# OMSI_TABLE_R12_v2.net
KiCad netlist of a schematic drawn in EAGLE
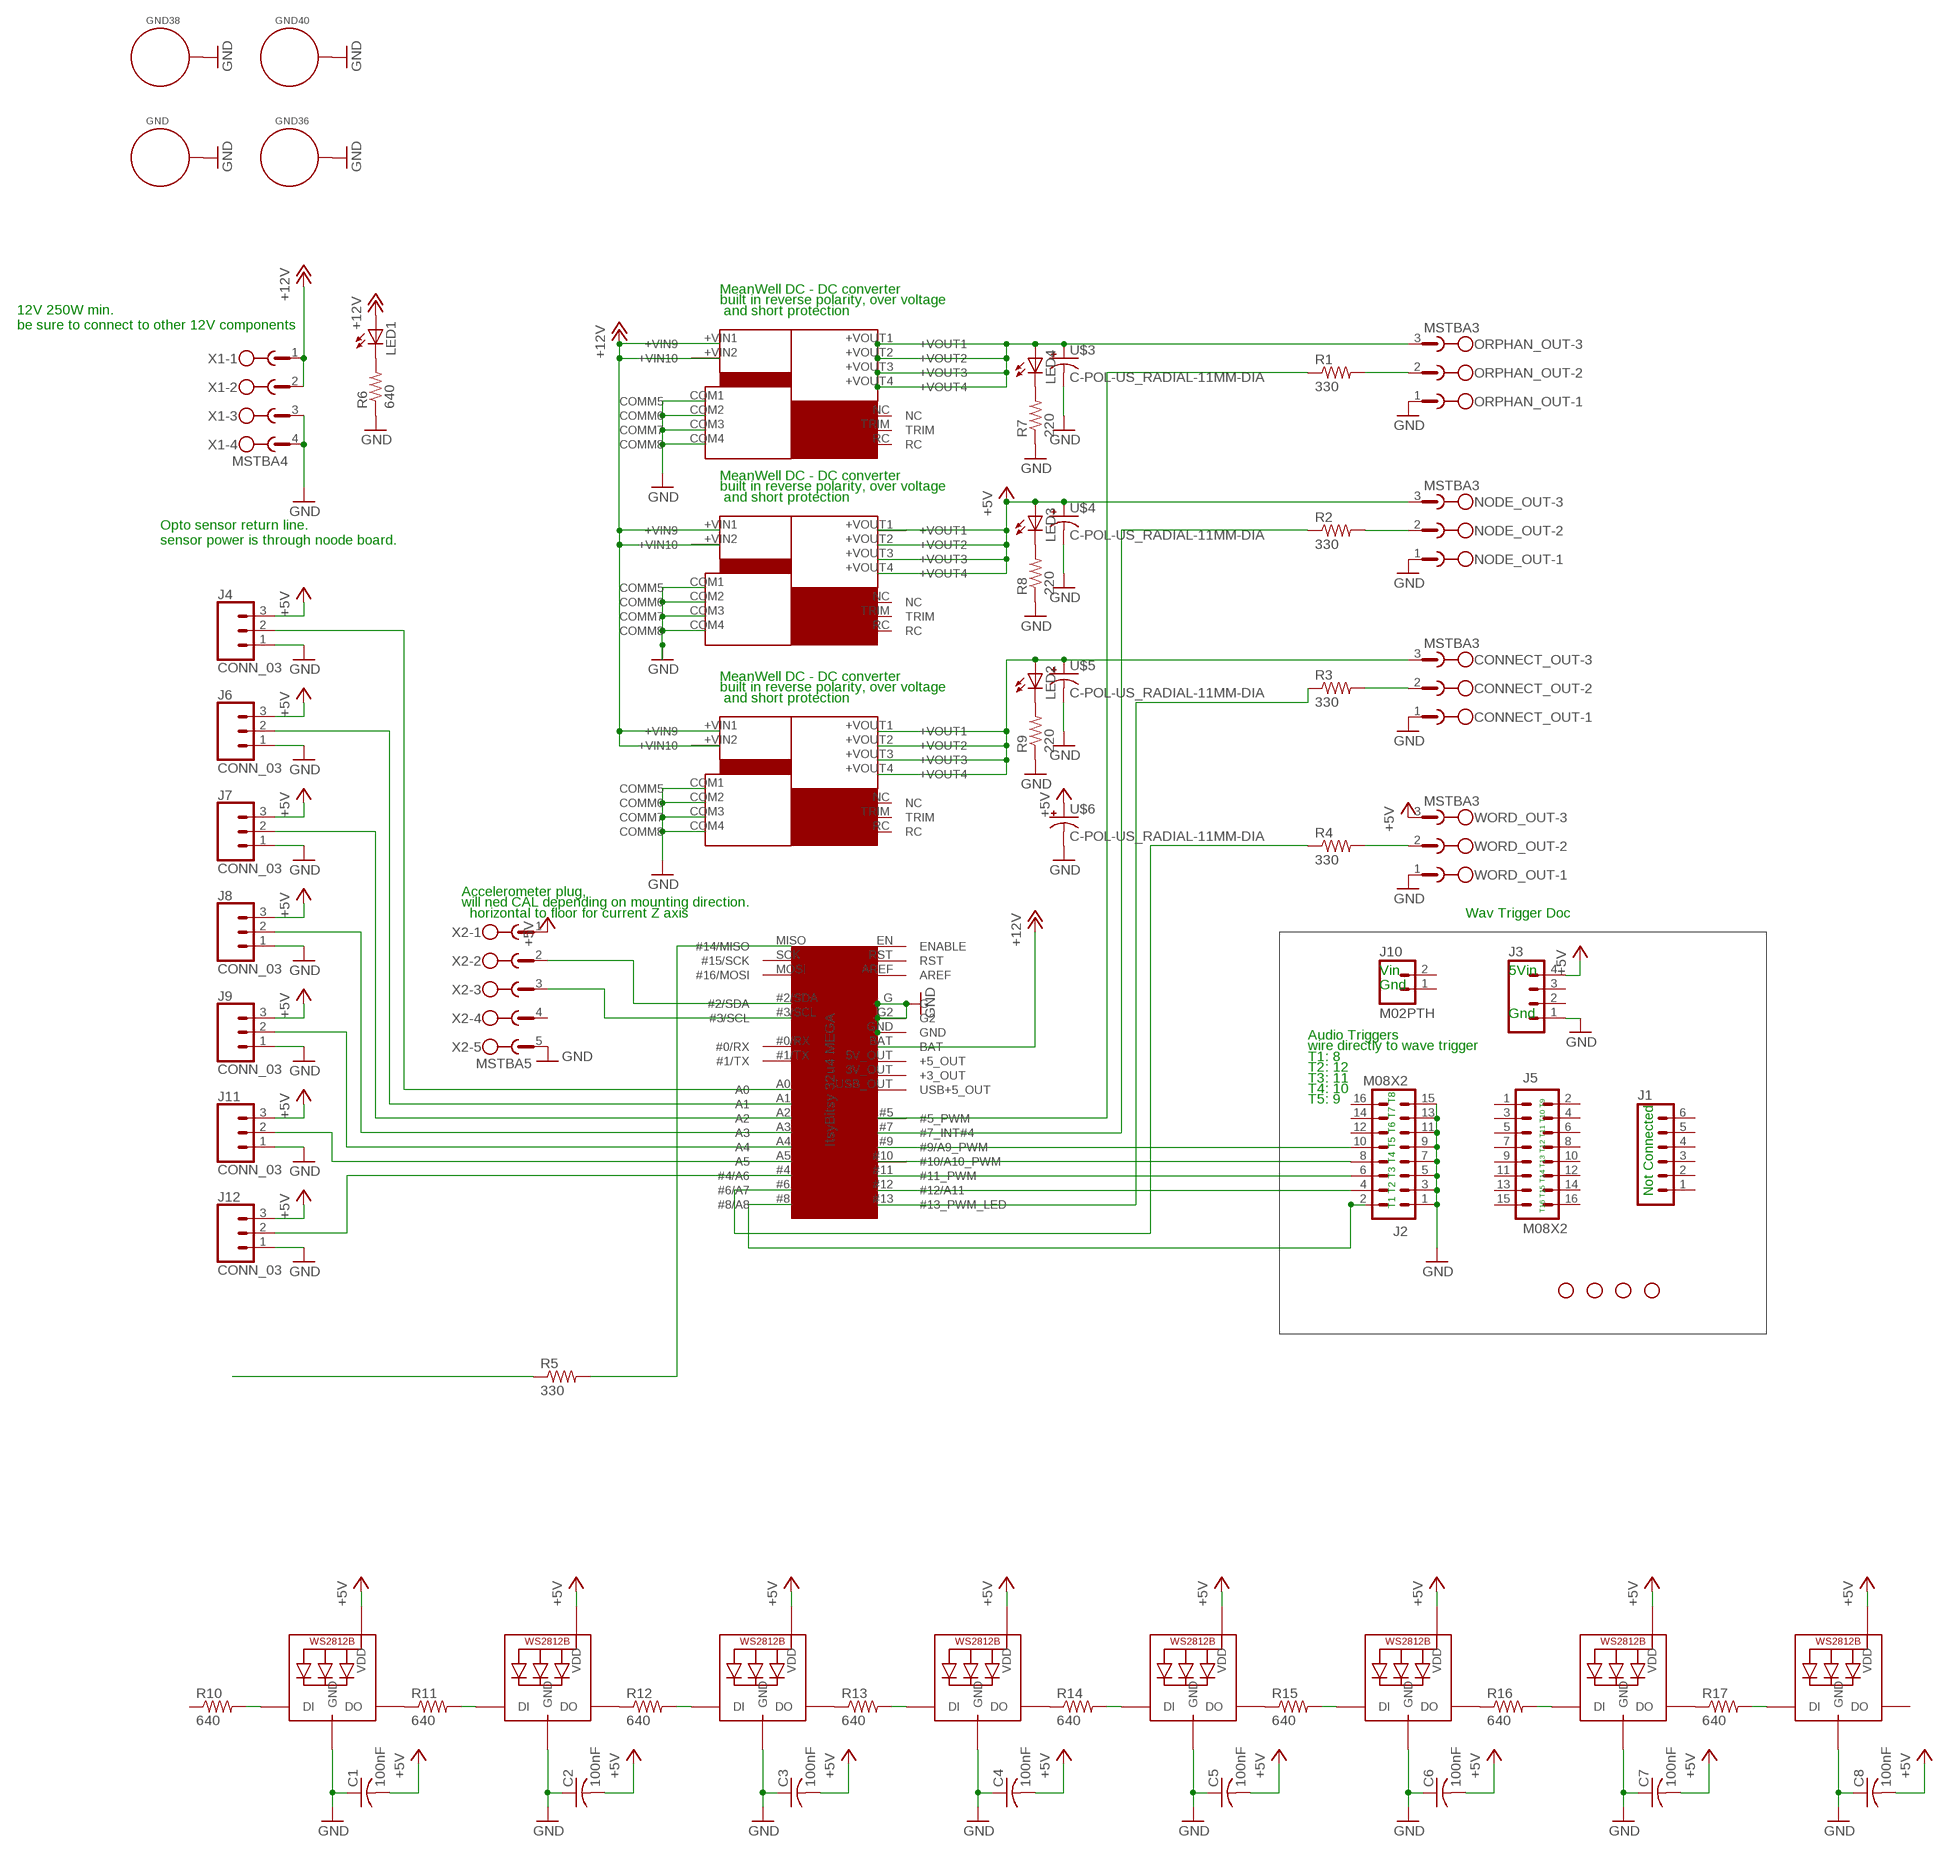
[diagram p0: schematic, sheet 1]

(export (version "E")
  (design (tool "Eeschema 10.0.6"))
  (components
    (comp (ref "C1")
      (value "100nF")
      (footprint "eagle-import:C0805")
      (libsource (lib "eagle-import") (part "C-USC0805"))
    )
    (comp (ref "C2")
      (value "100nF")
      (footprint "eagle-import:C0805")
      (libsource (lib "eagle-import") (part "C-USC0805"))
    )
    (comp (ref "C3")
      (value "100nF")
      (footprint "eagle-import:C0805")
      (libsource (lib "eagle-import") (part "C-USC0805"))
    )
    (comp (ref "C4")
      (value "100nF")
      (footprint "eagle-import:C0805")
      (libsource (lib "eagle-import") (part "C-USC0805"))
    )
    (comp (ref "C5")
      (value "100nF")
      (footprint "eagle-import:C0805")
      (libsource (lib "eagle-import") (part "C-USC0805"))
    )
    (comp (ref "C6")
      (value "100nF")
      (footprint "eagle-import:C0805")
      (libsource (lib "eagle-import") (part "C-USC0805"))
    )
    (comp (ref "C7")
      (value "100nF")
      (footprint "eagle-import:C0805")
      (libsource (lib "eagle-import") (part "C-USC0805"))
    )
    (comp (ref "C8")
      (value "100nF")
      (footprint "eagle-import:C0805")
      (libsource (lib "eagle-import") (part "C-USC0805"))
    )
    (comp (ref "CONNECT_OUT")
      (value "MSTBA3")
      (footprint "eagle-import:MSTBA3")
      (fields (field (name "MF") "FARNELL") (field (name "MPN") "1757255"))
      (libsource (lib "eagle-import") (part "MSTBA3"))
    )
    (comp (ref "GND")
      (value "STANDOFF_ELECTRICAL5-32")
      (footprint "eagle-import:STANDOFF_ELECTRICAL_5_32")
      (libsource (lib "eagle-import") (part "STANDOFF_ELECTRICAL5-32"))
    )
    (comp (ref "GND36")
      (value "STANDOFF_ELECTRICAL5-32")
      (footprint "eagle-import:STANDOFF_ELECTRICAL_5_32")
      (libsource (lib "eagle-import") (part "STANDOFF_ELECTRICAL5-32"))
    )
    (comp (ref "GND38")
      (value "STANDOFF_ELECTRICAL5-32")
      (footprint "eagle-import:STANDOFF_ELECTRICAL_5_32")
      (libsource (lib "eagle-import") (part "STANDOFF_ELECTRICAL5-32"))
    )
    (comp (ref "GND40")
      (value "STANDOFF_ELECTRICAL5-32")
      (footprint "eagle-import:STANDOFF_ELECTRICAL_5_32")
      (libsource (lib "eagle-import") (part "STANDOFF_ELECTRICAL5-32"))
    )
    (comp (ref "J1")
      (value "M06SIP")
      (footprint "eagle-import:1X06")
      (libsource (lib "eagle-import") (part "M06SIP"))
    )
    (comp (ref "J2")
      (value "M08X2")
      (footprint "eagle-import:2X8")
      (libsource (lib "eagle-import") (part "M08X2"))
    )
    (comp (ref "J3")
      (value "M04PTH")
      (footprint "eagle-import:1X04")
      (libsource (lib "eagle-import") (part "M04PTH"))
    )
    (comp (ref "J4")
      (value "CONN_03")
      (footprint "eagle-import:1X03_3.5MM_RA")
      (libsource (lib "eagle-import") (part "CONN_03"))
    )
    (comp (ref "J5")
      (value "M08X2")
      (footprint "eagle-import:2X8")
      (libsource (lib "eagle-import") (part "M08X2"))
    )
    (comp (ref "J6")
      (value "CONN_03")
      (footprint "eagle-import:1X03_3.5MM_RA")
      (libsource (lib "eagle-import") (part "CONN_03"))
    )
    (comp (ref "J7")
      (value "CONN_03")
      (footprint "eagle-import:1X03_3.5MM_RA")
      (libsource (lib "eagle-import") (part "CONN_03"))
    )
    (comp (ref "J8")
      (value "CONN_03")
      (footprint "eagle-import:1X03_3.5MM_RA")
      (libsource (lib "eagle-import") (part "CONN_03"))
    )
    (comp (ref "J9")
      (value "CONN_03")
      (footprint "eagle-import:1X03_3.5MM_RA")
      (libsource (lib "eagle-import") (part "CONN_03"))
    )
    (comp (ref "J10")
      (value "M02PTH")
      (footprint "eagle-import:1X02")
      (libsource (lib "eagle-import") (part "M02PTH"))
    )
    (comp (ref "J11")
      (value "CONN_03")
      (footprint "eagle-import:1X03_3.5MM_RA")
      (libsource (lib "eagle-import") (part "CONN_03"))
    )
    (comp (ref "J12")
      (value "CONN_03")
      (footprint "eagle-import:1X03_3.5MM_RA")
      (libsource (lib "eagle-import") (part "CONN_03"))
    )
    (comp (ref "LED1")
      (value "LEDCHIPLED_1206")
      (footprint "eagle-import:CHIPLED_1206")
      (libsource (lib "eagle-import") (part "LEDCHIPLED_1206"))
    )
    (comp (ref "LED2")
      (value "LEDCHIPLED_1206")
      (footprint "eagle-import:CHIPLED_1206")
      (libsource (lib "eagle-import") (part "LEDCHIPLED_1206"))
    )
    (comp (ref "LED3")
      (value "LEDCHIPLED_1206")
      (footprint "eagle-import:CHIPLED_1206")
      (libsource (lib "eagle-import") (part "LEDCHIPLED_1206"))
    )
    (comp (ref "LED4")
      (value "LEDCHIPLED_1206")
      (footprint "eagle-import:CHIPLED_1206")
      (libsource (lib "eagle-import") (part "LEDCHIPLED_1206"))
    )
    (comp (ref "LED5")
      (value "WS2812B")
      (footprint "eagle-import:WS2812D-F5")
      (libsource (lib "eagle-import") (part "WS2812B"))
    )
    (comp (ref "LED6")
      (value "WS2812B")
      (footprint "eagle-import:WS2812D-F5")
      (libsource (lib "eagle-import") (part "WS2812B"))
    )
    (comp (ref "LED7")
      (value "WS2812B")
      (footprint "eagle-import:WS2812D-F5")
      (libsource (lib "eagle-import") (part "WS2812B"))
    )
    (comp (ref "LED8")
      (value "WS2812B")
      (footprint "eagle-import:WS2812D-F5")
      (libsource (lib "eagle-import") (part "WS2812B"))
    )
    (comp (ref "LED9")
      (value "WS2812B")
      (footprint "eagle-import:WS2812D-F5")
      (libsource (lib "eagle-import") (part "WS2812B"))
    )
    (comp (ref "LED10")
      (value "WS2812B")
      (footprint "eagle-import:WS2812D-F5")
      (libsource (lib "eagle-import") (part "WS2812B"))
    )
    (comp (ref "LED11")
      (value "WS2812B")
      (footprint "eagle-import:WS2812D-F5")
      (libsource (lib "eagle-import") (part "WS2812B"))
    )
    (comp (ref "LED12")
      (value "WS2812B")
      (footprint "eagle-import:WS2812D-F5")
      (libsource (lib "eagle-import") (part "WS2812B"))
    )
    (comp (ref "MEANWELL_NID100_1")
      (value "MEANWELL_NID100")
      (footprint "eagle-import:MEANWELL_NID100")
      (libsource (lib "eagle-import") (part "MEANWELL_NID100"))
    )
    (comp (ref "MEANWELL_NID100_2")
      (value "MEANWELL_NID100")
      (footprint "eagle-import:MEANWELL_NID100")
      (libsource (lib "eagle-import") (part "MEANWELL_NID100"))
    )
    (comp (ref "MEANWELL_NID100_3")
      (value "MEANWELL_NID100")
      (footprint "eagle-import:MEANWELL_NID100")
      (libsource (lib "eagle-import") (part "MEANWELL_NID100"))
    )
    (comp (ref "NODE_OUT")
      (value "MSTBA3")
      (footprint "eagle-import:MSTBA3")
      (fields (field (name "MF") "FARNELL") (field (name "MPN") "1757255"))
      (libsource (lib "eagle-import") (part "MSTBA3"))
    )
    (comp (ref "ORPHAN_OUT")
      (value "MSTBA3")
      (footprint "eagle-import:MSTBA3")
      (fields (field (name "MF") "FARNELL") (field (name "MPN") "1757255"))
      (libsource (lib "eagle-import") (part "MSTBA3"))
    )
    (comp (ref "R1")
      (value "330")
      (footprint "eagle-import:RESAD1176W63L850D250B")
      (libsource (lib "eagle-import") (part "R-USAXIAL-11.7MM-PITCH_"))
    )
    (comp (ref "R2")
      (value "330")
      (footprint "eagle-import:RESAD1176W63L850D250B")
      (libsource (lib "eagle-import") (part "R-USAXIAL-11.7MM-PITCH_"))
    )
    (comp (ref "R3")
      (value "330")
      (footprint "eagle-import:RESAD1176W63L850D250B")
      (libsource (lib "eagle-import") (part "R-USAXIAL-11.7MM-PITCH_"))
    )
    (comp (ref "R4")
      (value "330")
      (footprint "eagle-import:RESAD1176W63L850D250B")
      (libsource (lib "eagle-import") (part "R-USAXIAL-11.7MM-PITCH_"))
    )
    (comp (ref "R5")
      (value "330")
      (footprint "eagle-import:RESAD1176W63L850D250B")
      (libsource (lib "eagle-import") (part "R-USAXIAL-11.7MM-PITCH_"))
    )
    (comp (ref "R6")
      (value "640")
      (footprint "eagle-import:R0805")
      (libsource (lib "eagle-import") (part "adafruit_420_R-US_R0805"))
    )
    (comp (ref "R7")
      (value "220")
      (footprint "eagle-import:R0805")
      (libsource (lib "eagle-import") (part "R-US_R0805"))
    )
    (comp (ref "R8")
      (value "220")
      (footprint "eagle-import:R0805")
      (libsource (lib "eagle-import") (part "R-US_R0805"))
    )
    (comp (ref "R9")
      (value "220")
      (footprint "eagle-import:R0805")
      (libsource (lib "eagle-import") (part "R-US_R0805"))
    )
    (comp (ref "R10")
      (value "640")
      (footprint "eagle-import:R0805")
      (libsource (lib "eagle-import") (part "adafruit_420_R-US_R0805"))
    )
    (comp (ref "R11")
      (value "640")
      (footprint "eagle-import:R0805")
      (libsource (lib "eagle-import") (part "adafruit_420_R-US_R0805"))
    )
    (comp (ref "R12")
      (value "640")
      (footprint "eagle-import:R0805")
      (libsource (lib "eagle-import") (part "adafruit_420_R-US_R0805"))
    )
    (comp (ref "R13")
      (value "640")
      (footprint "eagle-import:R0805")
      (libsource (lib "eagle-import") (part "adafruit_420_R-US_R0805"))
    )
    (comp (ref "R14")
      (value "640")
      (footprint "eagle-import:R0805")
      (libsource (lib "eagle-import") (part "adafruit_420_R-US_R0805"))
    )
    (comp (ref "R15")
      (value "640")
      (footprint "eagle-import:R0805")
      (libsource (lib "eagle-import") (part "adafruit_420_R-US_R0805"))
    )
    (comp (ref "R16")
      (value "640")
      (footprint "eagle-import:R0805")
      (libsource (lib "eagle-import") (part "adafruit_420_R-US_R0805"))
    )
    (comp (ref "R17")
      (value "640")
      (footprint "eagle-import:R0805")
      (libsource (lib "eagle-import") (part "adafruit_420_R-US_R0805"))
    )
    (comp (ref "STANDOFF5")
      (value "STAND-OFF")
      (footprint "eagle-import:STAND-OFF")
      (libsource (lib "eagle-import") (part "STAND-OFF"))
    )
    (comp (ref "STANDOFF6")
      (value "STAND-OFF")
      (footprint "eagle-import:STAND-OFF")
      (libsource (lib "eagle-import") (part "STAND-OFF"))
    )
    (comp (ref "STANDOFF7")
      (value "STAND-OFF")
      (footprint "eagle-import:STAND-OFF")
      (libsource (lib "eagle-import") (part "STAND-OFF"))
    )
    (comp (ref "STANDOFF8")
      (value "STAND-OFF")
      (footprint "eagle-import:STAND-OFF")
      (libsource (lib "eagle-import") (part "STAND-OFF"))
    )
    (comp (ref "U$1")
      (value "ITSYBITSY_32U4")
      (footprint "eagle-import:ITSYBITSY_32U4")
      (libsource (lib "eagle-import") (part "ITSYBITSY_32U4"))
    )
    (comp (ref "U$3")
      (value "C-POL-US_RADIAL-11MM-DIA")
      (footprint "eagle-import:CAPPRD508W65D1000H1100B")
      (libsource (lib "eagle-import") (part "C-POL-USRADIAL-11MM-DIA_"))
    )
    (comp (ref "U$4")
      (value "C-POL-US_RADIAL-11MM-DIA")
      (footprint "eagle-import:CAPPRD508W65D1000H1100B")
      (libsource (lib "eagle-import") (part "C-POL-USRADIAL-11MM-DIA_"))
    )
    (comp (ref "U$5")
      (value "C-POL-US_RADIAL-11MM-DIA")
      (footprint "eagle-import:CAPPRD508W65D1000H1100B")
      (libsource (lib "eagle-import") (part "C-POL-USRADIAL-11MM-DIA_"))
    )
    (comp (ref "U$6")
      (value "C-POL-US_RADIAL-11MM-DIA")
      (footprint "eagle-import:CAPPRD508W65D1000H1100B")
      (libsource (lib "eagle-import") (part "C-POL-USRADIAL-11MM-DIA_"))
    )
    (comp (ref "WORD_OUT")
      (value "MSTBA3")
      (footprint "eagle-import:MSTBA3")
      (fields (field (name "MF") "FARNELL") (field (name "MPN") "1757255"))
      (libsource (lib "eagle-import") (part "MSTBA3"))
    )
    (comp (ref "X1")
      (value "MSTBA4")
      (footprint "eagle-import:MSTBA4")
      (fields (field (name "MF") "FARNELL") (field (name "MPN") "1757268"))
      (libsource (lib "eagle-import") (part "MSTBA4"))
    )
    (comp (ref "X2")
      (value "MSTBA5")
      (footprint "eagle-import:MSTBA5")
      (fields (field (name "MPN") "1757271"))
      (libsource (lib "eagle-import") (part "MSTBA5"))
    )
  )
  (nets
    (net (code "1") (name "+5V") (class "Default")
      (node (ref "C1") (pin "2") (pinfunction "2_2") (pintype "passive"))
      (node (ref "C2") (pin "2") (pinfunction "2_2") (pintype "passive"))
      (node (ref "C3") (pin "2") (pinfunction "2_2") (pintype "passive"))
      (node (ref "C4") (pin "2") (pinfunction "2_2") (pintype "passive"))
      (node (ref "C5") (pin "2") (pinfunction "2_2") (pintype "passive"))
      (node (ref "C6") (pin "2") (pinfunction "2_2") (pintype "passive"))
      (node (ref "C7") (pin "2") (pinfunction "2_2") (pintype "passive"))
      (node (ref "C8") (pin "2") (pinfunction "2_2") (pintype "passive"))
      (node (ref "J11") (pin "3") (pinfunction "3_3") (pintype "passive"))
      (node (ref "J12") (pin "3") (pinfunction "3_3") (pintype "passive"))
      (node (ref "J3") (pin "4") (pinfunction "4_4") (pintype "passive"))
      (node (ref "J4") (pin "3") (pinfunction "3_3") (pintype "passive"))
      (node (ref "J6") (pin "3") (pinfunction "3_3") (pintype "passive"))
      (node (ref "J7") (pin "3") (pinfunction "3_3") (pintype "passive"))
      (node (ref "J8") (pin "3") (pinfunction "3_3") (pintype "passive"))
      (node (ref "J9") (pin "3") (pinfunction "3_3") (pintype "passive"))
      (node (ref "LED10") (pin "P$2") (pinfunction "VDD_P$2") (pintype "power_in"))
      (node (ref "LED11") (pin "P$2") (pinfunction "VDD_P$2") (pintype "power_in"))
      (node (ref "LED12") (pin "P$2") (pinfunction "VDD_P$2") (pintype "power_in"))
      (node (ref "LED3") (pin "A") (pinfunction "A_A") (pintype "passive"))
      (node (ref "LED5") (pin "P$2") (pinfunction "VDD_P$2") (pintype "power_in"))
      (node (ref "LED6") (pin "P$2") (pinfunction "VDD_P$2") (pintype "power_in"))
      (node (ref "LED7") (pin "P$2") (pinfunction "VDD_P$2") (pintype "power_in"))
      (node (ref "LED8") (pin "P$2") (pinfunction "VDD_P$2") (pintype "power_in"))
      (node (ref "LED9") (pin "P$2") (pinfunction "VDD_P$2") (pintype "power_in"))
      (node (ref "MEANWELL_NID100_3") (pin "+VOUT1") (pinfunction "+VOUT1_+VOUT1") (pintype "power_in"))
      (node (ref "MEANWELL_NID100_3") (pin "+VOUT2") (pinfunction "+VOUT2_+VOUT2") (pintype "power_in"))
      (node (ref "MEANWELL_NID100_3") (pin "+VOUT3") (pinfunction "+VOUT3_+VOUT3") (pintype "power_in"))
      (node (ref "MEANWELL_NID100_3") (pin "+VOUT4") (pinfunction "+VOUT4_+VOUT4") (pintype "power_in"))
      (node (ref "NODE_OUT") (pin "3") (pinfunction "1_3") (pintype "passive"))
      (node (ref "U$4") (pin "1") (pinfunction "+_1") (pintype "passive"))
      (node (ref "U$6") (pin "1") (pinfunction "+_1") (pintype "passive"))
      (node (ref "WORD_OUT") (pin "3") (pinfunction "1_3") (pintype "passive"))
      (node (ref "X2") (pin "1") (pinfunction "1_1") (pintype "passive"))
    )
    (net (code "2") (name "+12V") (class "Default")
      (node (ref "LED1") (pin "A") (pinfunction "A_A") (pintype "passive"))
      (node (ref "MEANWELL_NID100_1") (pin "+VIN1") (pinfunction "+VIN9_+VIN1") (pintype "power_in"))
      (node (ref "MEANWELL_NID100_1") (pin "+VIN2") (pinfunction "+VIN10_+VIN2") (pintype "power_in"))
      (node (ref "MEANWELL_NID100_2") (pin "+VIN1") (pinfunction "+VIN9_+VIN1") (pintype "power_in"))
      (node (ref "MEANWELL_NID100_2") (pin "+VIN2") (pinfunction "+VIN10_+VIN2") (pintype "power_in"))
      (node (ref "MEANWELL_NID100_3") (pin "+VIN1") (pinfunction "+VIN9_+VIN1") (pintype "power_in"))
      (node (ref "MEANWELL_NID100_3") (pin "+VIN2") (pinfunction "+VIN10_+VIN2") (pintype "power_in"))
      (node (ref "U$1") (pin "BAT") (pinfunction "BAT_BAT") (pintype "power_in"))
      (node (ref "X1") (pin "1") (pinfunction "1_1") (pintype "passive"))
      (node (ref "X1") (pin "2") (pinfunction "1_2") (pintype "passive"))
    )
    (net (code "3") (name "/+3_OUT") (class "Default")
      (node (ref "U$1") (pin "3V_OUT") (pinfunction "+3_OUT_3V_OUT") (pintype "power_in"))
    )
    (net (code "4") (name "/+5_OUT") (class "Default")
      (node (ref "U$1") (pin "5V_OUT") (pinfunction "+5_OUT_5V_OUT") (pintype "power_in"))
    )
    (net (code "5") (name "/AREF") (class "Default")
      (node (ref "U$1") (pin "AREF") (pinfunction "AREF_AREF") (pintype "power_in"))
    )
    (net (code "6") (name "/RST") (class "Default")
      (node (ref "U$1") (pin "RST") (pinfunction "RST_RST") (pintype "power_in"))
    )
    (net (code "7") (name "/USB+5_OUT") (class "Default")
      (node (ref "U$1") (pin "USB_OUT") (pinfunction "USB+5_OUT_USB_OUT") (pintype "power_in"))
    )
    (net (code "8") (name "GND") (class "Default")
      (node (ref "C1") (pin "1") (pinfunction "1_1") (pintype "passive"))
      (node (ref "C2") (pin "1") (pinfunction "1_1") (pintype "passive"))
      (node (ref "C3") (pin "1") (pinfunction "1_1") (pintype "passive"))
      (node (ref "C4") (pin "1") (pinfunction "1_1") (pintype "passive"))
      (node (ref "C5") (pin "1") (pinfunction "1_1") (pintype "passive"))
      (node (ref "C6") (pin "1") (pinfunction "1_1") (pintype "passive"))
      (node (ref "C7") (pin "1") (pinfunction "1_1") (pintype "passive"))
      (node (ref "C8") (pin "1") (pinfunction "1_1") (pintype "passive"))
      (node (ref "CONNECT_OUT") (pin "1") (pinfunction "1_1") (pintype "passive"))
      (node (ref "GND") (pin "P1") (pinfunction "P$1_P1") (pintype "bidirectional"))
      (node (ref "GND36") (pin "P1") (pinfunction "P$1_P1") (pintype "bidirectional"))
      (node (ref "GND38") (pin "P1") (pinfunction "P$1_P1") (pintype "bidirectional"))
      (node (ref "GND40") (pin "P1") (pinfunction "P$1_P1") (pintype "bidirectional"))
      (node (ref "J11") (pin "1") (pinfunction "1_1") (pintype "passive"))
      (node (ref "J12") (pin "1") (pinfunction "1_1") (pintype "passive"))
      (node (ref "J2") (pin "1") (pinfunction "1_1") (pintype "passive"))
      (node (ref "J2") (pin "11") (pinfunction "11_11") (pintype "passive"))
      (node (ref "J2") (pin "13") (pinfunction "13_13") (pintype "passive"))
      (node (ref "J2") (pin "15") (pinfunction "15_15") (pintype "passive"))
      (node (ref "J2") (pin "3") (pinfunction "3_3") (pintype "passive"))
      (node (ref "J2") (pin "5") (pinfunction "5_5") (pintype "passive"))
      (node (ref "J2") (pin "7") (pinfunction "7_7") (pintype "passive"))
      (node (ref "J2") (pin "9") (pinfunction "9_9") (pintype "passive"))
      (node (ref "J3") (pin "1") (pinfunction "1_1") (pintype "passive"))
      (node (ref "J4") (pin "1") (pinfunction "1_1") (pintype "passive"))
      (node (ref "J6") (pin "1") (pinfunction "1_1") (pintype "passive"))
      (node (ref "J7") (pin "1") (pinfunction "1_1") (pintype "passive"))
      (node (ref "J8") (pin "1") (pinfunction "1_1") (pintype "passive"))
      (node (ref "J9") (pin "1") (pinfunction "1_1") (pintype "passive"))
      (node (ref "LED10") (pin "P$3") (pinfunction "GND_P$3") (pintype "power_in"))
      (node (ref "LED11") (pin "P$3") (pinfunction "GND_P$3") (pintype "power_in"))
      (node (ref "LED12") (pin "P$3") (pinfunction "GND_P$3") (pintype "power_in"))
      (node (ref "LED5") (pin "P$3") (pinfunction "GND_P$3") (pintype "power_in"))
      (node (ref "LED6") (pin "P$3") (pinfunction "GND_P$3") (pintype "power_in"))
      (node (ref "LED7") (pin "P$3") (pinfunction "GND_P$3") (pintype "power_in"))
      (node (ref "LED8") (pin "P$3") (pinfunction "GND_P$3") (pintype "power_in"))
      (node (ref "LED9") (pin "P$3") (pinfunction "GND_P$3") (pintype "power_in"))
      (node (ref "MEANWELL_NID100_1") (pin "COM1") (pinfunction "COMM5_COM1") (pintype "power_in"))
      (node (ref "MEANWELL_NID100_1") (pin "COM2") (pinfunction "COMM6_COM2") (pintype "power_in"))
      (node (ref "MEANWELL_NID100_1") (pin "COM3") (pinfunction "COMM7_COM3") (pintype "power_in"))
      (node (ref "MEANWELL_NID100_1") (pin "COM4") (pinfunction "COMM8_COM4") (pintype "power_in"))
      (node (ref "MEANWELL_NID100_2") (pin "COM1") (pinfunction "COMM5_COM1") (pintype "power_in"))
      (node (ref "MEANWELL_NID100_2") (pin "COM2") (pinfunction "COMM6_COM2") (pintype "power_in"))
      (node (ref "MEANWELL_NID100_2") (pin "COM3") (pinfunction "COMM7_COM3") (pintype "power_in"))
      (node (ref "MEANWELL_NID100_2") (pin "COM4") (pinfunction "COMM8_COM4") (pintype "power_in"))
      (node (ref "MEANWELL_NID100_3") (pin "COM1") (pinfunction "COMM5_COM1") (pintype "power_in"))
      (node (ref "MEANWELL_NID100_3") (pin "COM2") (pinfunction "COMM6_COM2") (pintype "power_in"))
      (node (ref "MEANWELL_NID100_3") (pin "COM3") (pinfunction "COMM7_COM3") (pintype "power_in"))
      (node (ref "MEANWELL_NID100_3") (pin "COM4") (pinfunction "COMM8_COM4") (pintype "power_in"))
      (node (ref "NODE_OUT") (pin "1") (pinfunction "1_1") (pintype "passive"))
      (node (ref "ORPHAN_OUT") (pin "1") (pinfunction "1_1") (pintype "passive"))
      (node (ref "R6") (pin "1") (pinfunction "1_1") (pintype "passive"))
      (node (ref "R7") (pin "1") (pinfunction "1_1") (pintype "passive"))
      (node (ref "R8") (pin "1") (pinfunction "1_1") (pintype "passive"))
      (node (ref "R9") (pin "1") (pinfunction "1_1") (pintype "passive"))
      (node (ref "U$1") (pin "G") (pinfunction "G_G") (pintype "power_in"))
      (node (ref "U$1") (pin "G2") (pinfunction "G2_G2") (pintype "power_in"))
      (node (ref "U$1") (pin "GND") (pinfunction "GND_GND") (pintype "power_in"))
      (node (ref "U$3") (pin "2") (pinfunction "-_2") (pintype "passive"))
      (node (ref "U$4") (pin "2") (pinfunction "-_2") (pintype "passive"))
      (node (ref "U$5") (pin "2") (pinfunction "-_2") (pintype "passive"))
      (node (ref "U$6") (pin "2") (pinfunction "-_2") (pintype "passive"))
      (node (ref "WORD_OUT") (pin "1") (pinfunction "1_1") (pintype "passive"))
      (node (ref "X1") (pin "3") (pinfunction "1_3") (pintype "passive"))
      (node (ref "X1") (pin "4") (pinfunction "1_4") (pintype "passive"))
      (node (ref "X2") (pin "5") (pinfunction "1_5") (pintype "passive"))
    )
    (net (code "9") (name "Net-(CONNECT_OUTB-1)") (class "Default")
      (node (ref "CONNECT_OUT") (pin "2") (pinfunction "1_2") (pintype "passive"))
      (node (ref "R3") (pin "2") (pinfunction "2_2") (pintype "passive"))
    )
    (net (code "10") (name "Net-(CONNECT_OUTC-1)") (class "Default")
      (node (ref "CONNECT_OUT") (pin "3") (pinfunction "1_3") (pintype "passive"))
      (node (ref "LED2") (pin "A") (pinfunction "A_A") (pintype "passive"))
      (node (ref "MEANWELL_NID100_1") (pin "+VOUT1") (pinfunction "+VOUT1_+VOUT1") (pintype "power_in"))
      (node (ref "MEANWELL_NID100_1") (pin "+VOUT2") (pinfunction "+VOUT2_+VOUT2") (pintype "power_in"))
      (node (ref "MEANWELL_NID100_1") (pin "+VOUT3") (pinfunction "+VOUT3_+VOUT3") (pintype "power_in"))
      (node (ref "MEANWELL_NID100_1") (pin "+VOUT4") (pinfunction "+VOUT4_+VOUT4") (pintype "power_in"))
      (node (ref "U$5") (pin "1") (pinfunction "+_1") (pintype "passive"))
    )
    (net (code "11") (name "Net-(J4-Pad2)") (class "Default")
      (node (ref "J4") (pin "2") (pinfunction "2_2") (pintype "passive"))
      (node (ref "U$1") (pin "A0") (pinfunction "A0_A0") (pintype "bidirectional"))
    )
    (net (code "12") (name "Net-(J6-Pad2)") (class "Default")
      (node (ref "J6") (pin "2") (pinfunction "2_2") (pintype "passive"))
      (node (ref "U$1") (pin "A1") (pinfunction "A1_A1") (pintype "bidirectional"))
    )
    (net (code "13") (name "Net-(J7-Pad2)") (class "Default")
      (node (ref "J7") (pin "2") (pinfunction "2_2") (pintype "passive"))
      (node (ref "U$1") (pin "A2") (pinfunction "A2_A2") (pintype "bidirectional"))
    )
    (net (code "14") (name "Net-(J8-Pad2)") (class "Default")
      (node (ref "J8") (pin "2") (pinfunction "2_2") (pintype "passive"))
      (node (ref "U$1") (pin "A3") (pinfunction "A3_A3") (pintype "bidirectional"))
    )
    (net (code "15") (name "Net-(J9-Pad2)") (class "Default")
      (node (ref "J9") (pin "2") (pinfunction "2_2") (pintype "passive"))
      (node (ref "U$1") (pin "A4") (pinfunction "A4_A4") (pintype "bidirectional"))
    )
    (net (code "16") (name "Net-(J11-Pad2)") (class "Default")
      (node (ref "J11") (pin "2") (pinfunction "2_2") (pintype "passive"))
      (node (ref "U$1") (pin "A5") (pinfunction "A5_A5") (pintype "bidirectional"))
    )
    (net (code "17") (name "Net-(LED1-PadC)") (class "Default")
      (node (ref "LED1") (pin "C") (pinfunction "C_C") (pintype "passive"))
      (node (ref "R6") (pin "2") (pinfunction "2_2") (pintype "passive"))
    )
    (net (code "18") (name "Net-(LED2-PadC)") (class "Default")
      (node (ref "LED2") (pin "C") (pinfunction "C_C") (pintype "passive"))
      (node (ref "R9") (pin "2") (pinfunction "2_2") (pintype "passive"))
    )
    (net (code "19") (name "Net-(LED3-PadC)") (class "Default")
      (node (ref "LED3") (pin "C") (pinfunction "C_C") (pintype "passive"))
      (node (ref "R8") (pin "2") (pinfunction "2_2") (pintype "passive"))
    )
    (net (code "20") (name "Net-(LED4-PadC)") (class "Default")
      (node (ref "LED4") (pin "C") (pinfunction "C_C") (pintype "passive"))
      (node (ref "R7") (pin "2") (pinfunction "2_2") (pintype "passive"))
    )
    (net (code "21") (name "Net-(LED5-DI)") (class "Default")
      (node (ref "LED5") (pin "P$4") (pinfunction "DI_P$4") (pintype "input"))
      (node (ref "R10") (pin "2") (pinfunction "2_2") (pintype "passive"))
    )
    (net (code "22") (name "Net-(LED5-DO)") (class "Default")
      (node (ref "LED5") (pin "P$1") (pinfunction "DO_P$1") (pintype "output"))
      (node (ref "R11") (pin "1") (pinfunction "1_1") (pintype "passive"))
    )
    (net (code "23") (name "Net-(LED6-DI)") (class "Default")
      (node (ref "LED6") (pin "P$4") (pinfunction "DI_P$4") (pintype "input"))
      (node (ref "R11") (pin "2") (pinfunction "2_2") (pintype "passive"))
    )
    (net (code "24") (name "Net-(LED6-DO)") (class "Default")
      (node (ref "LED6") (pin "P$1") (pinfunction "DO_P$1") (pintype "output"))
      (node (ref "R12") (pin "1") (pinfunction "1_1") (pintype "passive"))
    )
    (net (code "25") (name "Net-(LED7-DI)") (class "Default")
      (node (ref "LED7") (pin "P$4") (pinfunction "DI_P$4") (pintype "input"))
      (node (ref "R12") (pin "2") (pinfunction "2_2") (pintype "passive"))
    )
    (net (code "26") (name "Net-(LED7-DO)") (class "Default")
      (node (ref "LED7") (pin "P$1") (pinfunction "DO_P$1") (pintype "output"))
      (node (ref "R13") (pin "1") (pinfunction "1_1") (pintype "passive"))
    )
    (net (code "27") (name "Net-(LED8-DI)") (class "Default")
      (node (ref "LED8") (pin "P$4") (pinfunction "DI_P$4") (pintype "input"))
      (node (ref "R13") (pin "2") (pinfunction "2_2") (pintype "passive"))
    )
    (net (code "28") (name "Net-(LED8-DO)") (class "Default")
      (node (ref "LED8") (pin "P$1") (pinfunction "DO_P$1") (pintype "output"))
      (node (ref "R14") (pin "1") (pinfunction "1_1") (pintype "passive"))
    )
    (net (code "29") (name "Net-(LED9-DI)") (class "Default")
      (node (ref "LED9") (pin "P$4") (pinfunction "DI_P$4") (pintype "input"))
      (node (ref "R14") (pin "2") (pinfunction "2_2") (pintype "passive"))
    )
    (net (code "30") (name "Net-(LED9-DO)") (class "Default")
      (node (ref "LED9") (pin "P$1") (pinfunction "DO_P$1") (pintype "output"))
      (node (ref "R15") (pin "1") (pinfunction "1_1") (pintype "passive"))
    )
    (net (code "31") (name "Net-(LED10-DI)") (class "Default")
      (node (ref "LED10") (pin "P$4") (pinfunction "DI_P$4") (pintype "input"))
      (node (ref "R15") (pin "2") (pinfunction "2_2") (pintype "passive"))
    )
    (net (code "32") (name "Net-(LED10-DO)") (class "Default")
      (node (ref "LED10") (pin "P$1") (pinfunction "DO_P$1") (pintype "output"))
      (node (ref "R16") (pin "1") (pinfunction "1_1") (pintype "passive"))
    )
    (net (code "33") (name "Net-(LED11-DI)") (class "Default")
      (node (ref "LED11") (pin "P$4") (pinfunction "DI_P$4") (pintype "input"))
      (node (ref "R16") (pin "2") (pinfunction "2_2") (pintype "passive"))
    )
    (net (code "34") (name "Net-(LED11-DO)") (class "Default")
      (node (ref "LED11") (pin "P$1") (pinfunction "DO_P$1") (pintype "output"))
      (node (ref "R17") (pin "1") (pinfunction "1_1") (pintype "passive"))
    )
    (net (code "35") (name "Net-(LED12-DI)") (class "Default")
      (node (ref "LED12") (pin "P$4") (pinfunction "DI_P$4") (pintype "input"))
      (node (ref "R17") (pin "2") (pinfunction "2_2") (pintype "passive"))
    )
    (net (code "36") (name "Net-(NODE_OUTB-1)") (class "Default")
      (node (ref "NODE_OUT") (pin "2") (pinfunction "1_2") (pintype "passive"))
      (node (ref "R2") (pin "2") (pinfunction "2_2") (pintype "passive"))
    )
    (net (code "37") (name "Net-(ORPHAN_OUTB-1)") (class "Default")
      (node (ref "ORPHAN_OUT") (pin "2") (pinfunction "1_2") (pintype "passive"))
      (node (ref "R1") (pin "2") (pinfunction "2_2") (pintype "passive"))
    )
    (net (code "38") (name "Net-(ORPHAN_OUTC-1)") (class "Default")
      (node (ref "LED4") (pin "A") (pinfunction "A_A") (pintype "passive"))
      (node (ref "MEANWELL_NID100_2") (pin "+VOUT1") (pinfunction "+VOUT1_+VOUT1") (pintype "power_in"))
      (node (ref "MEANWELL_NID100_2") (pin "+VOUT2") (pinfunction "+VOUT2_+VOUT2") (pintype "power_in"))
      (node (ref "MEANWELL_NID100_2") (pin "+VOUT3") (pinfunction "+VOUT3_+VOUT3") (pintype "power_in"))
      (node (ref "MEANWELL_NID100_2") (pin "+VOUT4") (pinfunction "+VOUT4_+VOUT4") (pintype "power_in"))
      (node (ref "ORPHAN_OUT") (pin "3") (pinfunction "1_3") (pintype "passive"))
      (node (ref "U$3") (pin "1") (pinfunction "+_1") (pintype "passive"))
    )
    (net (code "39") (name "Net-(U$1-#4{slash}A6)") (class "Default")
      (node (ref "J12") (pin "2") (pinfunction "2_2") (pintype "passive"))
      (node (ref "U$1") (pin "#4") (pinfunction "#4/A6_#4") (pintype "input"))
    )
    (net (code "40") (name "Net-(U$1-#5_PWM)") (class "Default")
      (node (ref "R1") (pin "1") (pinfunction "1_1") (pintype "passive"))
      (node (ref "U$1") (pin "#5") (pinfunction "#5_PWM_#5") (pintype "bidirectional"))
    )
    (net (code "41") (name "Net-(U$1-#6{slash}A7)") (class "Default")
      (node (ref "R4") (pin "1") (pinfunction "1_1") (pintype "passive"))
      (node (ref "U$1") (pin "#6") (pinfunction "#6/A7_#6") (pintype "bidirectional"))
    )
    (net (code "42") (name "Net-(U$1-#7_INT#4)") (class "Default")
      (node (ref "R2") (pin "1") (pinfunction "1_1") (pintype "passive"))
      (node (ref "U$1") (pin "#7") (pinfunction "#7_INT#4_#7") (pintype "bidirectional"))
    )
    (net (code "43") (name "Net-(U$1-#8{slash}A8)") (class "Default")
      (node (ref "J2") (pin "2") (pinfunction "2_2") (pintype "passive"))
      (node (ref "U$1") (pin "#8") (pinfunction "#8/A8_#8") (pintype "bidirectional"))
    )
    (net (code "44") (name "Net-(U$1-#9{slash}A9_PWM)") (class "Default")
      (node (ref "J2") (pin "10") (pinfunction "10_10") (pintype "passive"))
      (node (ref "U$1") (pin "#9") (pinfunction "#9/A9_PWM_#9") (pintype "bidirectional"))
    )
    (net (code "45") (name "Net-(U$1-#10{slash}A10_PWM)") (class "Default")
      (node (ref "J2") (pin "8") (pinfunction "8_8") (pintype "passive"))
      (node (ref "U$1") (pin "#10") (pinfunction "#10/A10_PWM_#10") (pintype "bidirectional"))
    )
    (net (code "46") (name "Net-(U$1-#11_PWM)") (class "Default")
      (node (ref "J2") (pin "6") (pinfunction "6_6") (pintype "passive"))
      (node (ref "U$1") (pin "#11") (pinfunction "#11_PWM_#11") (pintype "bidirectional"))
    )
    (net (code "47") (name "Net-(U$1-#12{slash}A11)") (class "Default")
      (node (ref "J2") (pin "4") (pinfunction "4_4") (pintype "passive"))
      (node (ref "U$1") (pin "#12") (pinfunction "#12/A11_#12") (pintype "bidirectional"))
    )
    (net (code "48") (name "Net-(U$1-#13_PWM_LED)") (class "Default")
      (node (ref "R3") (pin "1") (pinfunction "1_1") (pintype "passive"))
      (node (ref "U$1") (pin "#13") (pinfunction "#13_PWM_LED_#13") (pintype "bidirectional"))
    )
    (net (code "49") (name "Net-(U$1-#14{slash}MISO)") (class "Default")
      (node (ref "R5") (pin "2") (pinfunction "2_2") (pintype "passive"))
      (node (ref "U$1") (pin "MISO") (pinfunction "#14/MISO_MISO") (pintype "bidirectional"))
    )
    (net (code "50") (name "Net-(WORD_OUTB-1)") (class "Default")
      (node (ref "R4") (pin "2") (pinfunction "2_2") (pintype "passive"))
      (node (ref "WORD_OUT") (pin "2") (pinfunction "1_2") (pintype "passive"))
    )
    (net (code "51") (name "Net-(X2B-1)") (class "Default")
      (node (ref "U$1") (pin "#2/SDA") (pinfunction "#2/SDA_#2/SDA") (pintype "bidirectional"))
      (node (ref "X2") (pin "2") (pinfunction "1_2") (pintype "passive"))
    )
    (net (code "52") (name "Net-(X2C-1)") (class "Default")
      (node (ref "U$1") (pin "#3/SCL") (pinfunction "#3/SCL_#3/SCL") (pintype "bidirectional"))
      (node (ref "X2") (pin "3") (pinfunction "1_3") (pintype "passive"))
    )
    (net (code "53") (name "unconnected-(J1-Pad1)") (class "Default")
      (node (ref "J1") (pin "1") (pinfunction "1_1") (pintype "passive"))
    )
    (net (code "54") (name "unconnected-(J1-Pad2)") (class "Default")
      (node (ref "J1") (pin "2") (pinfunction "2_2") (pintype "passive"))
    )
    (net (code "55") (name "unconnected-(J1-Pad3)") (class "Default")
      (node (ref "J1") (pin "3") (pinfunction "3_3") (pintype "passive"))
    )
    (net (code "56") (name "unconnected-(J1-Pad4)") (class "Default")
      (node (ref "J1") (pin "4") (pinfunction "4_4") (pintype "passive"))
    )
    (net (code "57") (name "unconnected-(J1-Pad5)") (class "Default")
      (node (ref "J1") (pin "5") (pinfunction "5_5") (pintype "passive"))
    )
    (net (code "58") (name "unconnected-(J1-Pad6)") (class "Default")
      (node (ref "J1") (pin "6") (pinfunction "6_6") (pintype "passive"))
    )
    (net (code "59") (name "unconnected-(J2-Pad12)") (class "Default")
      (node (ref "J2") (pin "12") (pinfunction "12_12") (pintype "passive"))
    )
    (net (code "60") (name "unconnected-(J2-Pad14)") (class "Default")
      (node (ref "J2") (pin "14") (pinfunction "14_14") (pintype "passive"))
    )
    (net (code "61") (name "unconnected-(J2-Pad16)") (class "Default")
      (node (ref "J2") (pin "16") (pinfunction "16_16") (pintype "passive"))
    )
    (net (code "62") (name "unconnected-(J3-Pad2)") (class "Default")
      (node (ref "J3") (pin "2") (pinfunction "2_2") (pintype "passive"))
    )
    (net (code "63") (name "unconnected-(J3-Pad3)") (class "Default")
      (node (ref "J3") (pin "3") (pinfunction "3_3") (pintype "passive"))
    )
    (net (code "64") (name "unconnected-(J5-Pad1)") (class "Default")
      (node (ref "J5") (pin "1") (pinfunction "1_1") (pintype "passive"))
    )
    (net (code "65") (name "unconnected-(J5-Pad2)") (class "Default")
      (node (ref "J5") (pin "2") (pinfunction "2_2") (pintype "passive"))
    )
    (net (code "66") (name "unconnected-(J5-Pad3)") (class "Default")
      (node (ref "J5") (pin "3") (pinfunction "3_3") (pintype "passive"))
    )
    (net (code "67") (name "unconnected-(J5-Pad4)") (class "Default")
      (node (ref "J5") (pin "4") (pinfunction "4_4") (pintype "passive"))
    )
    (net (code "68") (name "unconnected-(J5-Pad5)") (class "Default")
      (node (ref "J5") (pin "5") (pinfunction "5_5") (pintype "passive"))
    )
    (net (code "69") (name "unconnected-(J5-Pad6)") (class "Default")
      (node (ref "J5") (pin "6") (pinfunction "6_6") (pintype "passive"))
    )
    (net (code "70") (name "unconnected-(J5-Pad7)") (class "Default")
      (node (ref "J5") (pin "7") (pinfunction "7_7") (pintype "passive"))
    )
    (net (code "71") (name "unconnected-(J5-Pad8)") (class "Default")
      (node (ref "J5") (pin "8") (pinfunction "8_8") (pintype "passive"))
    )
    (net (code "72") (name "unconnected-(J5-Pad9)") (class "Default")
      (node (ref "J5") (pin "9") (pinfunction "9_9") (pintype "passive"))
    )
    (net (code "73") (name "unconnected-(J5-Pad10)") (class "Default")
      (node (ref "J5") (pin "10") (pinfunction "10_10") (pintype "passive"))
    )
    (net (code "74") (name "unconnected-(J5-Pad11)") (class "Default")
      (node (ref "J5") (pin "11") (pinfunction "11_11") (pintype "passive"))
    )
    (net (code "75") (name "unconnected-(J5-Pad12)") (class "Default")
      (node (ref "J5") (pin "12") (pinfunction "12_12") (pintype "passive"))
    )
    (net (code "76") (name "unconnected-(J5-Pad13)") (class "Default")
      (node (ref "J5") (pin "13") (pinfunction "13_13") (pintype "passive"))
    )
    (net (code "77") (name "unconnected-(J5-Pad14)") (class "Default")
      (node (ref "J5") (pin "14") (pinfunction "14_14") (pintype "passive"))
    )
    (net (code "78") (name "unconnected-(J5-Pad15)") (class "Default")
      (node (ref "J5") (pin "15") (pinfunction "15_15") (pintype "passive"))
    )
    (net (code "79") (name "unconnected-(J5-Pad16)") (class "Default")
      (node (ref "J5") (pin "16") (pinfunction "16_16") (pintype "passive"))
    )
    (net (code "80") (name "unconnected-(J10-Pad1)") (class "Default")
      (node (ref "J10") (pin "1") (pinfunction "1_1") (pintype "passive"))
    )
    (net (code "81") (name "unconnected-(J10-Pad2)") (class "Default")
      (node (ref "J10") (pin "2") (pinfunction "2_2") (pintype "passive"))
    )
    (net (code "82") (name "unconnected-(LED12-DO-PadP$1)") (class "Default")
      (node (ref "LED12") (pin "P$1") (pinfunction "DO_P$1") (pintype "output"))
    )
    (net (code "83") (name "unconnected-(MEANWELL_NID100_1-PadNC)") (class "Default")
      (node (ref "MEANWELL_NID100_1") (pin "NC") (pinfunction "NC_NC") (pintype "no_connect"))
    )
    (net (code "84") (name "unconnected-(MEANWELL_NID100_1-PadRC)") (class "Default")
      (node (ref "MEANWELL_NID100_1") (pin "RC") (pinfunction "RC_RC") (pintype "no_connect"))
    )
    (net (code "85") (name "unconnected-(MEANWELL_NID100_1-PadTRIM)") (class "Default")
      (node (ref "MEANWELL_NID100_1") (pin "TRIM") (pinfunction "TRIM_TRIM") (pintype "no_connect"))
    )
    (net (code "86") (name "unconnected-(MEANWELL_NID100_2-PadNC)") (class "Default")
      (node (ref "MEANWELL_NID100_2") (pin "NC") (pinfunction "NC_NC") (pintype "no_connect"))
    )
    (net (code "87") (name "unconnected-(MEANWELL_NID100_2-PadRC)") (class "Default")
      (node (ref "MEANWELL_NID100_2") (pin "RC") (pinfunction "RC_RC") (pintype "no_connect"))
    )
    (net (code "88") (name "unconnected-(MEANWELL_NID100_2-PadTRIM)") (class "Default")
      (node (ref "MEANWELL_NID100_2") (pin "TRIM") (pinfunction "TRIM_TRIM") (pintype "no_connect"))
    )
    (net (code "89") (name "unconnected-(MEANWELL_NID100_3-PadNC)") (class "Default")
      (node (ref "MEANWELL_NID100_3") (pin "NC") (pinfunction "NC_NC") (pintype "no_connect"))
    )
    (net (code "90") (name "unconnected-(MEANWELL_NID100_3-PadRC)") (class "Default")
      (node (ref "MEANWELL_NID100_3") (pin "RC") (pinfunction "RC_RC") (pintype "no_connect"))
    )
    (net (code "91") (name "unconnected-(MEANWELL_NID100_3-PadTRIM)") (class "Default")
      (node (ref "MEANWELL_NID100_3") (pin "TRIM") (pinfunction "TRIM_TRIM") (pintype "no_connect"))
    )
    (net (code "92") (name "unconnected-(R5-Pad1)") (class "Default")
      (node (ref "R5") (pin "1") (pinfunction "1_1") (pintype "passive"))
    )
    (net (code "93") (name "unconnected-(R10-Pad1)") (class "Default")
      (node (ref "R10") (pin "1") (pinfunction "1_1") (pintype "passive"))
    )
    (net (code "94") (name "unconnected-(U$1-#15{slash}SCK-PadSCK)") (class "Default")
      (node (ref "U$1") (pin "SCK") (pinfunction "#15/SCK_SCK") (pintype "bidirectional"))
    )
    (net (code "95") (name "unconnected-(U$1-#16{slash}MOSI-PadMOSI)") (class "Default")
      (node (ref "U$1") (pin "MOSI") (pinfunction "#16/MOSI_MOSI") (pintype "bidirectional"))
    )
    (net (code "96") (name "unconnected-(U$1-ENABLE-PadEN)") (class "Default")
      (node (ref "U$1") (pin "EN") (pinfunction "ENABLE_EN") (pintype "input"))
    )
    (net (code "97") (name "unconnected-(U$1-Pad#0{slash}RX)") (class "Default")
      (node (ref "U$1") (pin "#0/RX") (pinfunction "#0/RX_#0/RX") (pintype "bidirectional"))
    )
    (net (code "98") (name "unconnected-(U$1-Pad#1{slash}TX)") (class "Default")
      (node (ref "U$1") (pin "#1/TX") (pinfunction "#1/TX_#1/TX") (pintype "bidirectional"))
    )
    (net (code "99") (name "unconnected-(X2D-1-Pad4)") (class "Default")
      (node (ref "X2") (pin "4") (pinfunction "1_4") (pintype "passive"))
    )
  )
)
